# sentinel_psionic.net
KiCad netlist of a schematic drawn in EAGLE
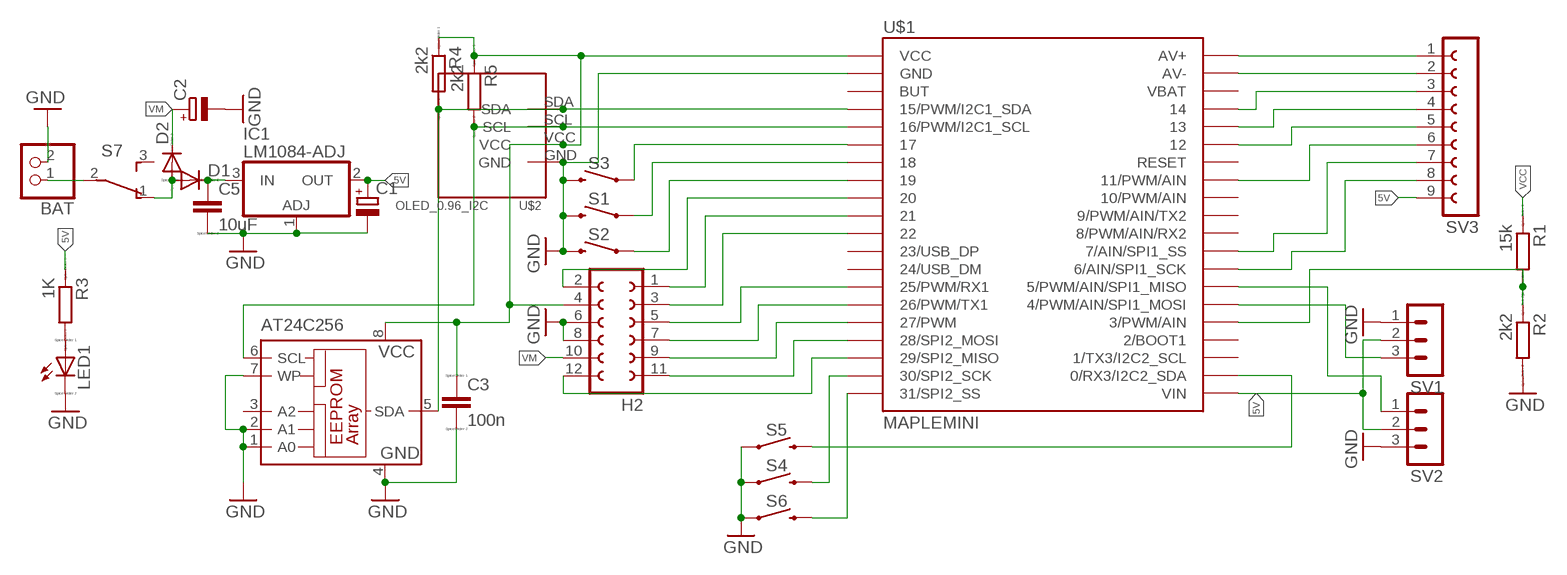
[diagram p0: schematic, sheet 1]

(export (version "E")
  (design (tool "Eeschema 10.0.6"))
  (components
    (comp (ref "AT24C256")
      (value "24AA01SN")
      (footprint "eagle-import:SO-08")
      (fields (field (name "MF") "MICROCHIP") (field (name "MPN") "24AA01/SN"))
      (libsource (lib "eagle-import") (part "24SNAA01"))
    )
    (comp (ref "BAT")
      (value "PINHD-1X2")
      (footprint "eagle-import:1X02")
      (libsource (lib "eagle-import") (part "PINHD-1X2"))
    )
    (comp (ref "C1")
      (value "CPOL-EU153CLV-0605")
      (footprint "eagle-import:153CLV-0605")
      (libsource (lib "eagle-import") (part "CPOL-EU153CLV-0605"))
    )
    (comp (ref "C2")
      (value "CPOL-EU153CLV-0605")
      (footprint "eagle-import:153CLV-0605")
      (libsource (lib "eagle-import") (part "CPOL-EU153CLV-0605"))
    )
    (comp (ref "C3")
      (value "100n")
      (footprint "eagle-import:C1206")
      (libsource (lib "eagle-import") (part "CC1206"))
    )
    (comp (ref "C5")
      (value "10uF")
      (footprint "eagle-import:C1206")
      (libsource (lib "eagle-import") (part "eagle-ltspice_217_CC1206"))
    )
    (comp (ref "D1")
      (value "DIODE-DO-214AC")
      (footprint "eagle-import:DO-214AC")
      (libsource (lib "eagle-import") (part "DIODE-DO-214AC"))
    )
    (comp (ref "D2")
      (value "DIODE-DO-214AC")
      (footprint "eagle-import:DO-214AC")
      (libsource (lib "eagle-import") (part "DIODE-DO-214AC"))
    )
    (comp (ref "H2")
      (value "FE06-2")
      (footprint "eagle-import:FE06-2")
      (libsource (lib "eagle-import") (part "FE06-2"))
    )
    (comp (ref "IC1")
      (value "LM1084-ADJ")
      (footprint "eagle-import:TO263-3")
      (libsource (lib "eagle-import") (part "LM1084-ADJ"))
    )
    (comp (ref "LED1")
      (value "LED_E")
      (footprint "eagle-import:LED_1206")
      (libsource (lib "eagle-import") (part "LED_E"))
    )
    (comp (ref "R1")
      (value "15k")
      (footprint "eagle-import:R1206")
      (libsource (lib "eagle-import") (part "RR1206"))
    )
    (comp (ref "R2")
      (value "2k2")
      (footprint "eagle-import:R1206")
      (libsource (lib "eagle-import") (part "RR1206"))
    )
    (comp (ref "R3")
      (value "1K")
      (footprint "eagle-import:R1206")
      (libsource (lib "eagle-import") (part "RR1206"))
    )
    (comp (ref "R4")
      (value "2k2")
      (footprint "eagle-import:R1206")
      (libsource (lib "eagle-import") (part "RR1206"))
    )
    (comp (ref "R5")
      (value "2k2")
      (footprint "eagle-import:R1206")
      (libsource (lib "eagle-import") (part "RR1206"))
    )
    (comp (ref "S1")
      (value "MOMENTARY-SWITCH-SPST-SMD-6.0X3.5MM")
      (footprint "eagle-import:TACTILE_SWITCH_SMD_6.0X3.5MM")
      (libsource (lib "eagle-import") (part "MOMENTARY-SWITCH-SPST-SMD-6.0X3.5MM"))
    )
    (comp (ref "S2")
      (value "MOMENTARY-SWITCH-SPST-SMD-6.0X3.5MM")
      (footprint "eagle-import:TACTILE_SWITCH_SMD_6.0X3.5MM")
      (libsource (lib "eagle-import") (part "MOMENTARY-SWITCH-SPST-SMD-6.0X3.5MM"))
    )
    (comp (ref "S3")
      (value "MOMENTARY-SWITCH-SPST-SMD-6.0X3.5MM")
      (footprint "eagle-import:TACTILE_SWITCH_SMD_6.0X3.5MM")
      (libsource (lib "eagle-import") (part "MOMENTARY-SWITCH-SPST-SMD-6.0X3.5MM"))
    )
    (comp (ref "S4")
      (value "MOMENTARY-SWITCH-SPST-SMD-6.0X3.5MM")
      (footprint "eagle-import:TACTILE_SWITCH_SMD_6.0X3.5MM")
      (libsource (lib "eagle-import") (part "MOMENTARY-SWITCH-SPST-SMD-6.0X3.5MM"))
    )
    (comp (ref "S5")
      (value "MOMENTARY-SWITCH-SPST-SMD-6.0X3.5MM")
      (footprint "eagle-import:TACTILE_SWITCH_SMD_6.0X3.5MM")
      (libsource (lib "eagle-import") (part "MOMENTARY-SWITCH-SPST-SMD-6.0X3.5MM"))
    )
    (comp (ref "S6")
      (value "MOMENTARY-SWITCH-SPST-SMD-6.0X3.5MM")
      (footprint "eagle-import:TACTILE_SWITCH_SMD_6.0X3.5MM")
      (libsource (lib "eagle-import") (part "MOMENTARY-SWITCH-SPST-SMD-6.0X3.5MM"))
    )
    (comp (ref "S7")
      (value "TL36PO")
      (footprint "eagle-import:TL3XPO")
      (libsource (lib "eagle-import") (part "TL36PO"))
    )
    (comp (ref "SV1")
      (value "MA03-1")
      (footprint "eagle-import:MA03-1")
      (libsource (lib "eagle-import") (part "MA03-1"))
    )
    (comp (ref "SV2")
      (value "MA03-1")
      (footprint "eagle-import:MA03-1")
      (libsource (lib "eagle-import") (part "MA03-1"))
    )
    (comp (ref "SV3")
      (value "FE09-1")
      (footprint "eagle-import:FE09")
      (libsource (lib "eagle-import") (part "FE09-1"))
    )
    (comp (ref "U$1")
      (value "MAPLEMINI")
      (footprint "eagle-import:20-DIP")
      (libsource (lib "eagle-import") (part "MAPLEMINI"))
    )
    (comp (ref "U$2")
      (value "OLED_0.96_I2C")
      (footprint "eagle-import:OLED_0.96_I2C")
      (libsource (lib "eagle-import") (part "OLED_0.96_I2C"))
    )
  )
  (nets
    (net (code "1") (name "5V") (class "Default")
      (node (ref "C1") (pin "+") (pinfunction "+_+") (pintype "passive"))
      (node (ref "IC1") (pin "2") (pinfunction "OUT_2") (pintype "output"))
      (node (ref "R3") (pin "1") (pinfunction "1_1") (pintype "passive"))
      (node (ref "SV1") (pin "2") (pinfunction "2_2") (pintype "passive"))
      (node (ref "SV2") (pin "2") (pinfunction "2_2") (pintype "passive"))
      (node (ref "SV3") (pin "9") (pinfunction "9_9") (pintype "passive"))
      (node (ref "U$1") (pin "21") (pinfunction "VIN_21") (pintype "bidirectional"))
    )
    (net (code "2") (name "GND") (class "Default")
      (node (ref "AT24C256") (pin "1") (pinfunction "A0_1") (pintype "input"))
      (node (ref "AT24C256") (pin "2") (pinfunction "A1_2") (pintype "input"))
      (node (ref "AT24C256") (pin "4") (pinfunction "GND_4") (pintype "power_in"))
      (node (ref "AT24C256") (pin "7") (pinfunction "WP_7") (pintype "input"))
      (node (ref "BAT") (pin "2") (pinfunction "2_2") (pintype "passive"))
      (node (ref "C1") (pin "-") (pinfunction "-_-") (pintype "passive"))
      (node (ref "C2") (pin "-") (pinfunction "-_-") (pintype "passive"))
      (node (ref "C3") (pin "2") (pinfunction "2_2") (pintype "passive"))
      (node (ref "C5") (pin "2") (pinfunction "2_2") (pintype "passive"))
      (node (ref "H2") (pin "6") (pinfunction "6_6") (pintype "passive"))
      (node (ref "H2") (pin "8") (pinfunction "8_8") (pintype "passive"))
      (node (ref "IC1") (pin "1") (pinfunction "ADJ_1") (pintype "passive"))
      (node (ref "LED1") (pin "C") (pinfunction "C_C") (pintype "passive"))
      (node (ref "R2") (pin "2") (pinfunction "2_2") (pintype "passive"))
      (node (ref "S1") (pin "2") (pinfunction "2_2") (pintype "passive"))
      (node (ref "S2") (pin "2") (pinfunction "2_2") (pintype "passive"))
      (node (ref "S3") (pin "2") (pinfunction "2_2") (pintype "passive"))
      (node (ref "S4") (pin "1") (pinfunction "1_1") (pintype "passive"))
      (node (ref "S5") (pin "1") (pinfunction "1_1") (pintype "passive"))
      (node (ref "S6") (pin "1") (pinfunction "1_1") (pintype "passive"))
      (node (ref "SV1") (pin "1") (pinfunction "1_1") (pintype "passive"))
      (node (ref "SV2") (pin "3") (pinfunction "3_3") (pintype "passive"))
      (node (ref "U$1") (pin "2") (pinfunction "GND_2") (pintype "bidirectional"))
      (node (ref "U$2") (pin "GND") (pinfunction "GND_GND") (pintype "bidirectional"))
    )
    (net (code "3") (name "Net-(AT24C256-SCL)") (class "Default")
      (node (ref "AT24C256") (pin "6") (pinfunction "SCL_6") (pintype "input"))
      (node (ref "R5") (pin "2") (pinfunction "2_2") (pintype "passive"))
      (node (ref "U$1") (pin "5") (pinfunction "16/PWM/I2C1_SCL_5") (pintype "bidirectional"))
      (node (ref "U$2") (pin "SCL") (pinfunction "SCL_SCL") (pintype "bidirectional"))
    )
    (net (code "4") (name "Net-(AT24C256-SDA)") (class "Default")
      (node (ref "AT24C256") (pin "5") (pinfunction "SDA_5") (pintype "bidirectional"))
      (node (ref "R4") (pin "2") (pinfunction "2_2") (pintype "passive"))
      (node (ref "U$1") (pin "4") (pinfunction "15/PWM/I2C1_SDA_4") (pintype "bidirectional"))
      (node (ref "U$2") (pin "SDA") (pinfunction "SDA_SDA") (pintype "bidirectional"))
    )
    (net (code "5") (name "Net-(AT24C256-VCC)") (class "Default")
      (node (ref "AT24C256") (pin "8") (pinfunction "VCC_8") (pintype "power_in"))
      (node (ref "C3") (pin "1") (pinfunction "1_1") (pintype "passive"))
      (node (ref "H2") (pin "4") (pinfunction "4_4") (pintype "passive"))
      (node (ref "R4") (pin "1") (pinfunction "1_1") (pintype "passive"))
      (node (ref "R5") (pin "1") (pinfunction "1_1") (pintype "passive"))
      (node (ref "U$1") (pin "1") (pinfunction "VCC_1") (pintype "bidirectional"))
      (node (ref "U$2") (pin "VCC") (pinfunction "VCC_VCC") (pintype "bidirectional"))
    )
    (net (code "6") (name "Net-(IC1-IN)") (class "Default")
      (node (ref "C5") (pin "1") (pinfunction "1_1") (pintype "passive"))
      (node (ref "D1") (pin "C") (pinfunction "C_C") (pintype "passive"))
      (node (ref "IC1") (pin "3") (pinfunction "IN_3") (pintype "input"))
    )
    (net (code "7") (name "Net-(LED1-PadA)") (class "Default")
      (node (ref "LED1") (pin "A") (pinfunction "A_A") (pintype "passive"))
      (node (ref "R3") (pin "2") (pinfunction "2_2") (pintype "passive"))
    )
    (net (code "8") (name "Net-(S7-P)") (class "Default")
      (node (ref "BAT") (pin "1") (pinfunction "1_1") (pintype "passive"))
      (node (ref "S7") (pin "2") (pinfunction "P_2") (pintype "passive"))
    )
    (net (code "9") (name "Net-(U$1-0{slash}RX3{slash}I2C2_SDA)") (class "Default")
      (node (ref "S5") (pin "2") (pinfunction "2_2") (pintype "passive"))
      (node (ref "U$1") (pin "22") (pinfunction "0/RX3/I2C2_SDA_22") (pintype "bidirectional"))
    )
    (net (code "10") (name "Net-(U$1-3{slash}PWM{slash}AIN)") (class "Default")
      (node (ref "R1") (pin "2") (pinfunction "2_2") (pintype "passive"))
      (node (ref "R2") (pin "1") (pinfunction "1_1") (pintype "passive"))
      (node (ref "U$1") (pin "25") (pinfunction "3/PWM/AIN_25") (pintype "bidirectional"))
    )
    (net (code "11") (name "Net-(U$1-4{slash}PWM{slash}AIN{slash}SPI1_MOSI)") (class "Default")
      (node (ref "SV1") (pin "3") (pinfunction "3_3") (pintype "passive"))
      (node (ref "U$1") (pin "26") (pinfunction "4/PWM/AIN/SPI1_MOSI_26") (pintype "bidirectional"))
    )
    (net (code "12") (name "Net-(U$1-5{slash}PWM{slash}AIN{slash}SPI1_MISO)") (class "Default")
      (node (ref "SV2") (pin "1") (pinfunction "1_1") (pintype "passive"))
      (node (ref "U$1") (pin "27") (pinfunction "5/PWM/AIN/SPI1_MISO_27") (pintype "bidirectional"))
    )
    (net (code "13") (name "Net-(U$1-6{slash}AIN{slash}SPI1_SCK)") (class "Default")
      (node (ref "SV3") (pin "8") (pinfunction "8_8") (pintype "passive"))
      (node (ref "U$1") (pin "28") (pinfunction "6/AIN/SPI1_SCK_28") (pintype "bidirectional"))
    )
    (net (code "14") (name "Net-(U$1-7{slash}AIN{slash}SPI1_SS)") (class "Default")
      (node (ref "SV3") (pin "7") (pinfunction "7_7") (pintype "passive"))
      (node (ref "U$1") (pin "29") (pinfunction "7/AIN/SPI1_SS_29") (pintype "bidirectional"))
    )
    (net (code "15") (name "Net-(U$1-11{slash}PWM{slash}AIN)") (class "Default")
      (node (ref "SV3") (pin "6") (pinfunction "6_6") (pintype "passive"))
      (node (ref "U$1") (pin "33") (pinfunction "11/PWM/AIN_33") (pintype "bidirectional"))
    )
    (net (code "16") (name "Net-(U$1-12)") (class "Default")
      (node (ref "SV3") (pin "5") (pinfunction "5_5") (pintype "passive"))
      (node (ref "U$1") (pin "35") (pinfunction "12_35") (pintype "bidirectional"))
    )
    (net (code "17") (name "Net-(U$1-13)") (class "Default")
      (node (ref "SV3") (pin "4") (pinfunction "4_4") (pintype "passive"))
      (node (ref "U$1") (pin "36") (pinfunction "13_36") (pintype "bidirectional"))
    )
    (net (code "18") (name "Net-(U$1-14)") (class "Default")
      (node (ref "SV3") (pin "3") (pinfunction "3_3") (pintype "passive"))
      (node (ref "U$1") (pin "37") (pinfunction "14_37") (pintype "bidirectional"))
    )
    (net (code "19") (name "Net-(U$1-17)") (class "Default")
      (node (ref "S3") (pin "1") (pinfunction "1_1") (pintype "passive"))
      (node (ref "U$1") (pin "6") (pinfunction "17_6") (pintype "bidirectional"))
    )
    (net (code "20") (name "Net-(U$1-18)") (class "Default")
      (node (ref "S1") (pin "1") (pinfunction "1_1") (pintype "passive"))
      (node (ref "U$1") (pin "7") (pinfunction "18_7") (pintype "bidirectional"))
    )
    (net (code "21") (name "Net-(U$1-19)") (class "Default")
      (node (ref "S2") (pin "1") (pinfunction "1_1") (pintype "passive"))
      (node (ref "U$1") (pin "8") (pinfunction "19_8") (pintype "bidirectional"))
    )
    (net (code "22") (name "Net-(U$1-20)") (class "Default")
      (node (ref "H2") (pin "2") (pinfunction "2_2") (pintype "passive"))
      (node (ref "U$1") (pin "9") (pinfunction "20_9") (pintype "bidirectional"))
    )
    (net (code "23") (name "Net-(U$1-21)") (class "Default")
      (node (ref "H2") (pin "1") (pinfunction "1_1") (pintype "passive"))
      (node (ref "U$1") (pin "10") (pinfunction "21_10") (pintype "bidirectional"))
    )
    (net (code "24") (name "Net-(U$1-22)") (class "Default")
      (node (ref "H2") (pin "3") (pinfunction "3_3") (pintype "passive"))
      (node (ref "U$1") (pin "11") (pinfunction "22_11") (pintype "bidirectional"))
    )
    (net (code "25") (name "Net-(U$1-25{slash}PWM{slash}RX1)") (class "Default")
      (node (ref "H2") (pin "5") (pinfunction "5_5") (pintype "passive"))
      (node (ref "U$1") (pin "14") (pinfunction "25/PWM/RX1_14") (pintype "bidirectional"))
    )
    (net (code "26") (name "Net-(U$1-26{slash}PWM{slash}TX1)") (class "Default")
      (node (ref "H2") (pin "7") (pinfunction "7_7") (pintype "passive"))
      (node (ref "U$1") (pin "15") (pinfunction "26/PWM/TX1_15") (pintype "bidirectional"))
    )
    (net (code "27") (name "Net-(U$1-27{slash}PWM)") (class "Default")
      (node (ref "H2") (pin "9") (pinfunction "9_9") (pintype "passive"))
      (node (ref "U$1") (pin "16") (pinfunction "27/PWM_16") (pintype "bidirectional"))
    )
    (net (code "28") (name "Net-(U$1-28{slash}SPI2_MOSI)") (class "Default")
      (node (ref "H2") (pin "11") (pinfunction "11_11") (pintype "passive"))
      (node (ref "U$1") (pin "17") (pinfunction "28/SPI2_MOSI_17") (pintype "bidirectional"))
    )
    (net (code "29") (name "Net-(U$1-29{slash}SPI2_MISO)") (class "Default")
      (node (ref "H2") (pin "12") (pinfunction "12_12") (pintype "passive"))
      (node (ref "U$1") (pin "18") (pinfunction "29/SPI2_MISO_18") (pintype "bidirectional"))
    )
    (net (code "30") (name "Net-(U$1-30{slash}SPI2_SCK)") (class "Default")
      (node (ref "S4") (pin "2") (pinfunction "2_2") (pintype "passive"))
      (node (ref "U$1") (pin "19") (pinfunction "30/SPI2_SCK_19") (pintype "bidirectional"))
    )
    (net (code "31") (name "Net-(U$1-31{slash}SPI2_SS)") (class "Default")
      (node (ref "S6") (pin "2") (pinfunction "2_2") (pintype "passive"))
      (node (ref "U$1") (pin "20") (pinfunction "31/SPI2_SS_20") (pintype "bidirectional"))
    )
    (net (code "32") (name "Net-(U$1-AV+)") (class "Default")
      (node (ref "SV3") (pin "1") (pinfunction "1_1") (pintype "passive"))
      (node (ref "U$1") (pin "40") (pinfunction "AV+_40") (pintype "bidirectional"))
    )
    (net (code "33") (name "Net-(U$1-AV-)") (class "Default")
      (node (ref "SV3") (pin "2") (pinfunction "2_2") (pintype "passive"))
      (node (ref "U$1") (pin "39") (pinfunction "AV-_39") (pintype "bidirectional"))
    )
    (net (code "34") (name "VCC") (class "Default")
      (node (ref "D1") (pin "A") (pinfunction "A_A") (pintype "passive"))
      (node (ref "D2") (pin "A") (pinfunction "A_A") (pintype "passive"))
      (node (ref "R1") (pin "1") (pinfunction "1_1") (pintype "passive"))
      (node (ref "S7") (pin "1") (pinfunction "O_1") (pintype "passive"))
    )
    (net (code "35") (name "VM") (class "Default")
      (node (ref "C2") (pin "+") (pinfunction "+_+") (pintype "passive"))
      (node (ref "D2") (pin "C") (pinfunction "C_C") (pintype "passive"))
      (node (ref "H2") (pin "10") (pinfunction "10_10") (pintype "passive"))
    )
    (net (code "36") (name "unconnected-(AT24C256-A2-Pad3)") (class "Default")
      (node (ref "AT24C256") (pin "3") (pinfunction "A2_3") (pintype "input"))
    )
    (net (code "37") (name "unconnected-(S7-S-Pad3)") (class "Default")
      (node (ref "S7") (pin "3") (pinfunction "S_3") (pintype "passive"))
    )
    (net (code "38") (name "unconnected-(U$1-1{slash}TX3{slash}I2C2_SCL-Pad23)") (class "Default")
      (node (ref "U$1") (pin "23") (pinfunction "1/TX3/I2C2_SCL_23") (pintype "bidirectional"))
    )
    (net (code "39") (name "unconnected-(U$1-2{slash}BOOT1-Pad24)") (class "Default")
      (node (ref "U$1") (pin "24") (pinfunction "2/BOOT1_24") (pintype "bidirectional"))
    )
    (net (code "40") (name "unconnected-(U$1-8{slash}PWM{slash}AIN{slash}RX2-Pad30)") (class "Default")
      (node (ref "U$1") (pin "30") (pinfunction "8/PWM/AIN/RX2_30") (pintype "bidirectional"))
    )
    (net (code "41") (name "unconnected-(U$1-9{slash}PWM{slash}AIN{slash}TX2-Pad31)") (class "Default")
      (node (ref "U$1") (pin "31") (pinfunction "9/PWM/AIN/TX2_31") (pintype "bidirectional"))
    )
    (net (code "42") (name "unconnected-(U$1-10{slash}PWM{slash}AIN-Pad32)") (class "Default")
      (node (ref "U$1") (pin "32") (pinfunction "10/PWM/AIN_32") (pintype "bidirectional"))
    )
    (net (code "43") (name "unconnected-(U$1-23{slash}USB_DP-Pad12)") (class "Default")
      (node (ref "U$1") (pin "12") (pinfunction "23/USB_DP_12") (pintype "bidirectional"))
    )
    (net (code "44") (name "unconnected-(U$1-24{slash}USB_DM-Pad13)") (class "Default")
      (node (ref "U$1") (pin "13") (pinfunction "24/USB_DM_13") (pintype "bidirectional"))
    )
    (net (code "45") (name "unconnected-(U$1-BUT-Pad3)") (class "Default")
      (node (ref "U$1") (pin "3") (pinfunction "BUT_3") (pintype "bidirectional"))
    )
    (net (code "46") (name "unconnected-(U$1-RESET-Pad34)") (class "Default")
      (node (ref "U$1") (pin "34") (pinfunction "RESET_34") (pintype "bidirectional"))
    )
    (net (code "47") (name "unconnected-(U$1-VBAT-Pad38)") (class "Default")
      (node (ref "U$1") (pin "38") (pinfunction "VBAT_38") (pintype "bidirectional"))
    )
  )
)
